# miniadsb.net
KiCad netlist of a schematic drawn in EAGLE
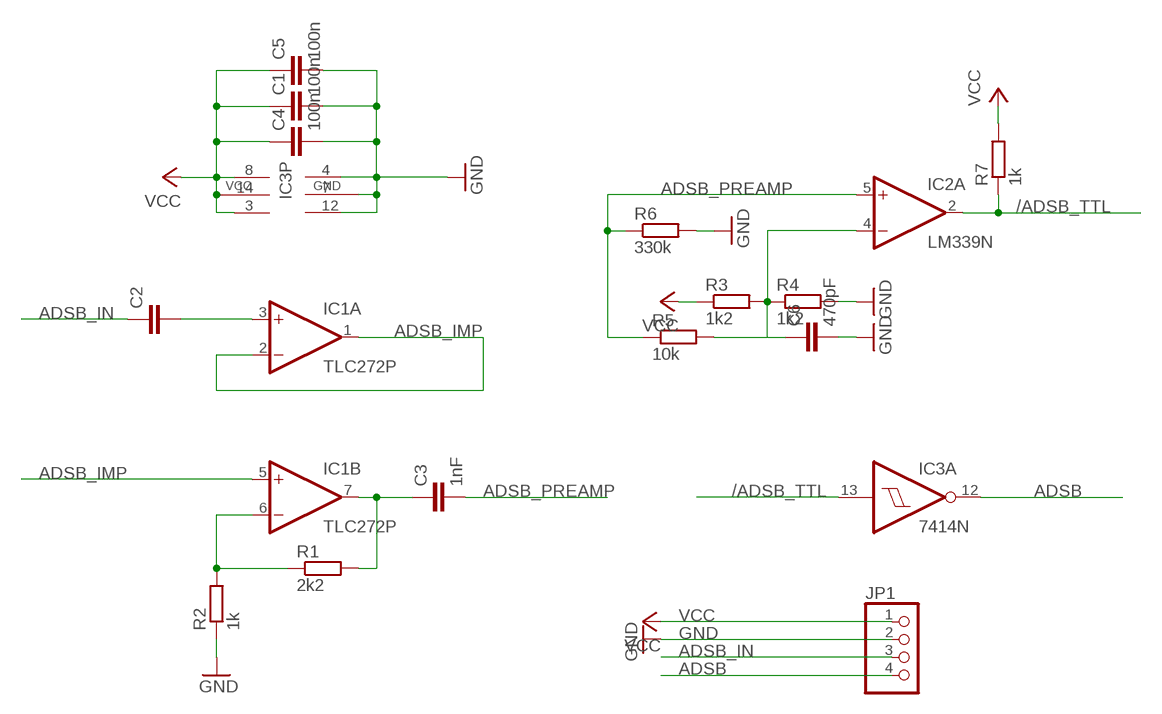
[diagram p0: schematic, sheet 1]

(export (version "E")
  (design (tool "Eeschema 10.0.6"))
  (components
    (comp (ref "C1")
      (value "100n")
      (footprint "eagle-import:C0805")
      (libsource (lib "eagle-import") (part "C-EUC0805"))
    )
    (comp (ref "C2")
      (value "C-EUC0805")
      (footprint "eagle-import:C0805")
      (libsource (lib "eagle-import") (part "C-EUC0805"))
    )
    (comp (ref "C3")
      (value "1nF")
      (footprint "eagle-import:C0805")
      (libsource (lib "eagle-import") (part "C-EUC0805"))
    )
    (comp (ref "C4")
      (value "100n")
      (footprint "eagle-import:C0805")
      (libsource (lib "eagle-import") (part "C-EUC0805"))
    )
    (comp (ref "C5")
      (value "100n")
      (footprint "eagle-import:C0805")
      (libsource (lib "eagle-import") (part "C-EUC0805"))
    )
    (comp (ref "C6")
      (value "470pF")
      (footprint "eagle-import:C0805")
      (libsource (lib "eagle-import") (part "C-EUC0805"))
    )
    (comp (ref "IC1")
      (value "TLC272P")
      (footprint "eagle-import:DIL08")
      (libsource (lib "eagle-import") (part "TLC272P"))
    )
    (comp (ref "IC2")
      (value "LM339N")
      (footprint "eagle-import:DIL14")
      (libsource (lib "eagle-import") (part "LM339N"))
    )
    (comp (ref "IC3")
      (value "7414N")
      (footprint "eagle-import:DIL14")
      (libsource (lib "eagle-import") (part "7414N"))
    )
    (comp (ref "JP1")
      (value "PINHD-1X4")
      (footprint "eagle-import:1X04")
      (libsource (lib "eagle-import") (part "PINHD-1X4"))
    )
    (comp (ref "R1")
      (value "2k2")
      (footprint "eagle-import:R0805")
      (libsource (lib "eagle-import") (part "resistor_R-EU_R0805"))
    )
    (comp (ref "R2")
      (value "1k")
      (footprint "eagle-import:R0805")
      (libsource (lib "eagle-import") (part "resistor_R-EU_R0805"))
    )
    (comp (ref "R3")
      (value "1k2")
      (footprint "eagle-import:R0805")
      (libsource (lib "eagle-import") (part "resistor_R-EU_R0805"))
    )
    (comp (ref "R4")
      (value "1k2")
      (footprint "eagle-import:R0805")
      (libsource (lib "eagle-import") (part "resistor_R-EU_R0805"))
    )
    (comp (ref "R5")
      (value "10k")
      (footprint "eagle-import:R0805")
      (libsource (lib "eagle-import") (part "resistor_R-EU_R0805"))
    )
    (comp (ref "R6")
      (value "330k")
      (footprint "eagle-import:R0805")
      (libsource (lib "eagle-import") (part "resistor_R-EU_R0805"))
    )
    (comp (ref "R7")
      (value "1k")
      (footprint "eagle-import:R0603")
      (libsource (lib "eagle-import") (part "R-EU_R0603"))
    )
  )
  (nets
    (net (code "1") (name "/ADSB") (class "Default")
      (node (ref "IC3") (pin "12") (pinfunction "O_12") (pintype "output"))
      (node (ref "JP1") (pin "4") (pinfunction "4_4") (pintype "passive"))
    )
    (net (code "2") (name "/ADSB_IMP") (class "Default")
      (node (ref "IC1") (pin "1") (pinfunction "OUT_1") (pintype "output"))
      (node (ref "IC1") (pin "2") (pinfunction "-IN_2") (pintype "input"))
      (node (ref "IC1") (pin "5") (pinfunction "+IN_5") (pintype "input"))
    )
    (net (code "3") (name "/ADSB_IN") (class "Default")
      (node (ref "C2") (pin "1") (pinfunction "1_1") (pintype "passive"))
      (node (ref "JP1") (pin "3") (pinfunction "3_3") (pintype "passive"))
    )
    (net (code "4") (name "/ADSB_PREAMP") (class "Default")
      (node (ref "C3") (pin "2") (pinfunction "2_2") (pintype "passive"))
      (node (ref "IC2") (pin "5") (pinfunction "+IN_5") (pintype "input"))
      (node (ref "R5") (pin "1") (pinfunction "1_1") (pintype "passive"))
      (node (ref "R6") (pin "1") (pinfunction "1_1") (pintype "passive"))
    )
    (net (code "5") (name "/{slash}ADSB_TTL") (class "Default")
      (node (ref "IC2") (pin "2") (pinfunction "OUT_2") (pintype "open_collector"))
      (node (ref "IC3") (pin "13") (pinfunction "I_13") (pintype "input"))
      (node (ref "R7") (pin "1") (pinfunction "1_1") (pintype "passive"))
    )
    (net (code "6") (name "GND") (class "Default")
      (node (ref "C1") (pin "2") (pinfunction "2_2") (pintype "passive"))
      (node (ref "C4") (pin "2") (pinfunction "2_2") (pintype "passive"))
      (node (ref "C5") (pin "2") (pinfunction "2_2") (pintype "passive"))
      (node (ref "C6") (pin "2") (pinfunction "2_2") (pintype "passive"))
      (node (ref "IC1") (pin "4") (pinfunction "V-_4") (pintype "power_in"))
      (node (ref "IC2") (pin "12") (pinfunction "GND_12") (pintype "power_in"))
      (node (ref "IC3") (pin "7") (pinfunction "GND_7") (pintype "power_in"))
      (node (ref "JP1") (pin "2") (pinfunction "2_2") (pintype "passive"))
      (node (ref "R2") (pin "1") (pinfunction "1_1") (pintype "passive"))
      (node (ref "R4") (pin "2") (pinfunction "2_2") (pintype "passive"))
      (node (ref "R6") (pin "2") (pinfunction "2_2") (pintype "passive"))
    )
    (net (code "7") (name "Net-(IC1A-+IN)") (class "Default")
      (node (ref "C2") (pin "2") (pinfunction "2_2") (pintype "passive"))
      (node (ref "IC1") (pin "3") (pinfunction "+IN_3") (pintype "input"))
    )
    (net (code "8") (name "Net-(IC1B--IN)") (class "Default")
      (node (ref "IC1") (pin "6") (pinfunction "-IN_6") (pintype "input"))
      (node (ref "R1") (pin "1") (pinfunction "1_1") (pintype "passive"))
      (node (ref "R2") (pin "2") (pinfunction "2_2") (pintype "passive"))
    )
    (net (code "9") (name "Net-(IC1B-OUT)") (class "Default")
      (node (ref "C3") (pin "1") (pinfunction "1_1") (pintype "passive"))
      (node (ref "IC1") (pin "7") (pinfunction "OUT_7") (pintype "output"))
      (node (ref "R1") (pin "2") (pinfunction "2_2") (pintype "passive"))
    )
    (net (code "10") (name "Net-(IC2A--IN)") (class "Default")
      (node (ref "C6") (pin "1") (pinfunction "1_1") (pintype "passive"))
      (node (ref "IC2") (pin "4") (pinfunction "-IN_4") (pintype "input"))
      (node (ref "R3") (pin "2") (pinfunction "2_2") (pintype "passive"))
      (node (ref "R4") (pin "1") (pinfunction "1_1") (pintype "passive"))
      (node (ref "R5") (pin "2") (pinfunction "2_2") (pintype "passive"))
    )
    (net (code "11") (name "VCC") (class "Default")
      (node (ref "C1") (pin "1") (pinfunction "1_1") (pintype "passive"))
      (node (ref "C4") (pin "1") (pinfunction "1_1") (pintype "passive"))
      (node (ref "C5") (pin "1") (pinfunction "1_1") (pintype "passive"))
      (node (ref "IC1") (pin "8") (pinfunction "V+_8") (pintype "power_in"))
      (node (ref "IC2") (pin "3") (pinfunction "V+_3") (pintype "power_in"))
      (node (ref "IC3") (pin "14") (pinfunction "VCC_14") (pintype "power_in"))
      (node (ref "JP1") (pin "1") (pinfunction "1_1") (pintype "passive"))
      (node (ref "R3") (pin "1") (pinfunction "1_1") (pintype "passive"))
      (node (ref "R7") (pin "2") (pinfunction "2_2") (pintype "passive"))
    )
  )
)
